# 1__schdoc.net
KiCad netlist of a schematic drawn in Altium Designer
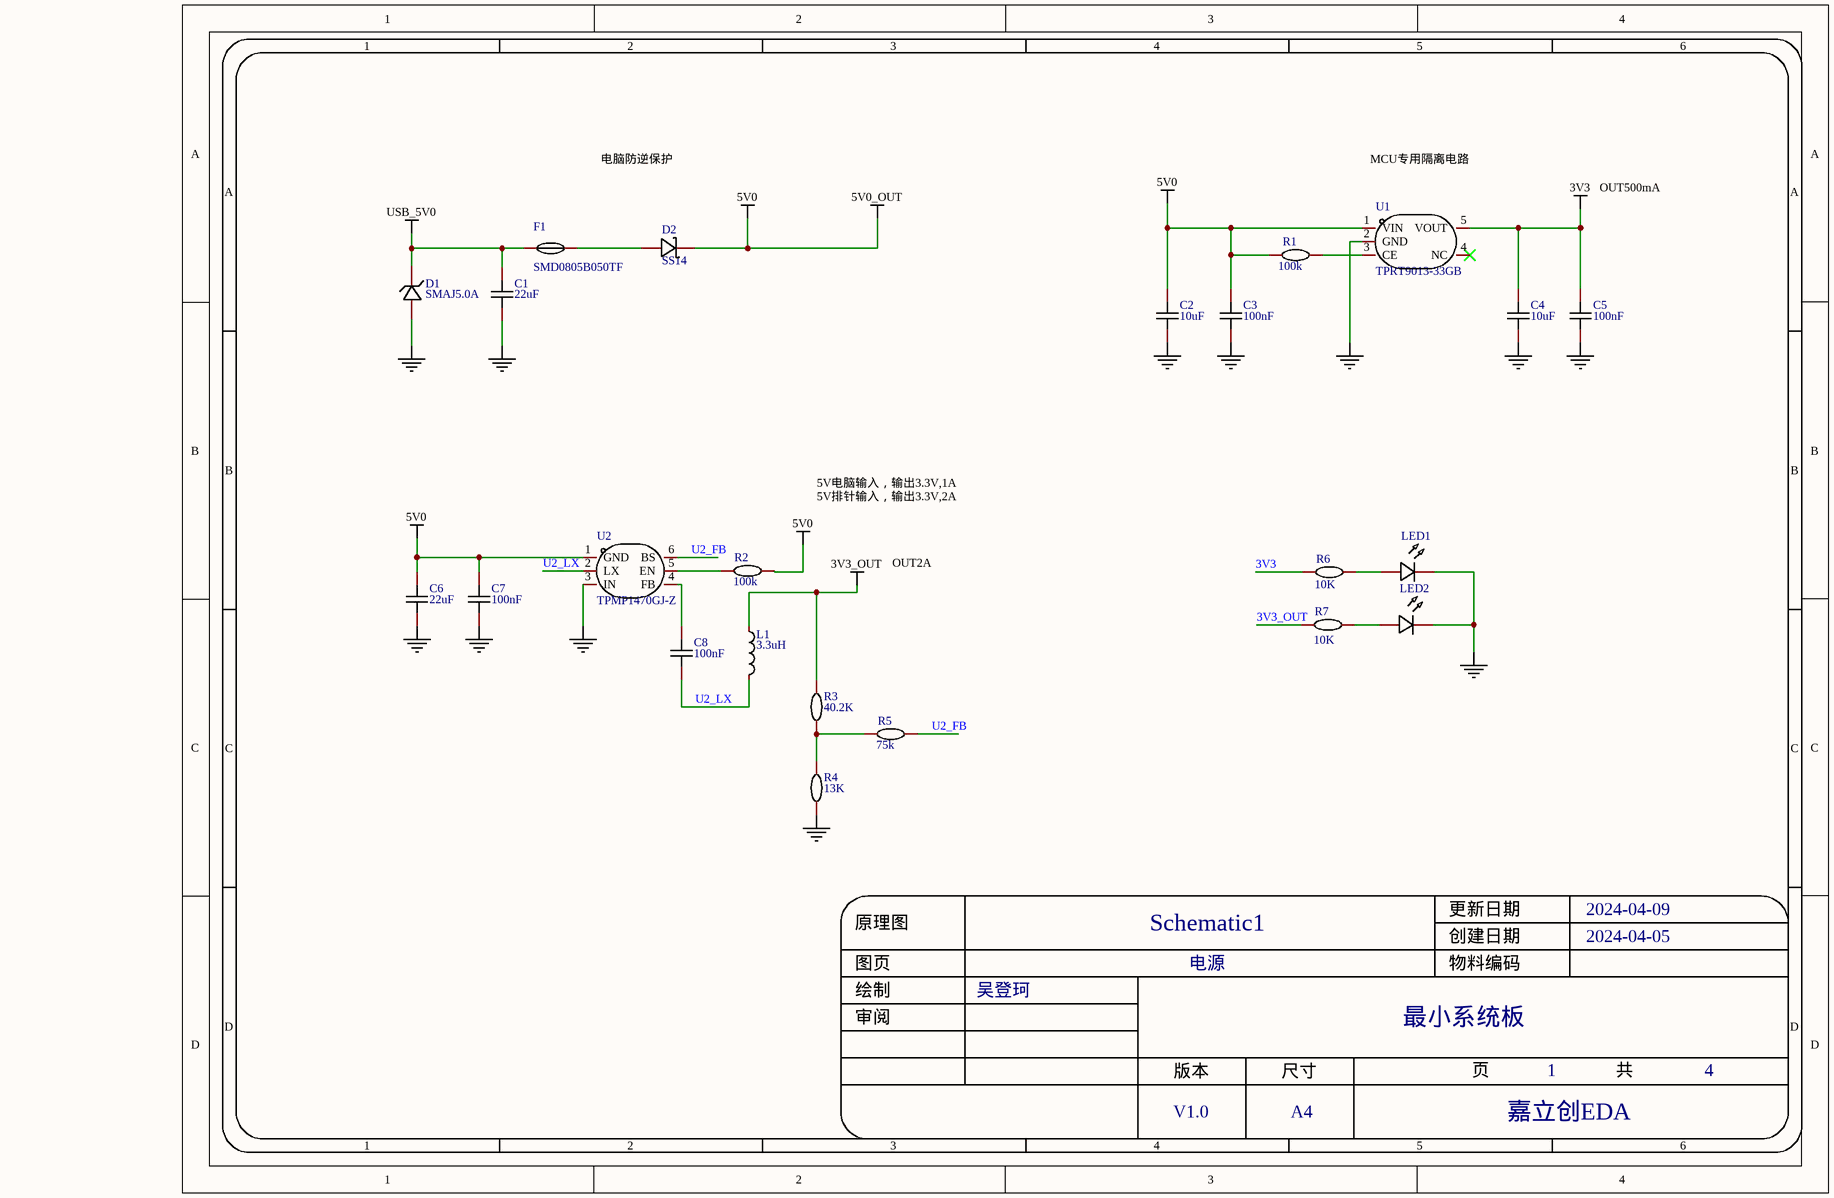
[diagram p0: 1_电源.schdoc.schdoc]

(export (version "E")
  (design (tool "Eeschema 10.0.6"))
  (components
    (comp (ref "C1")
      (value "22uF")
      (footprint "C1206")
      (fields (field (name "NAME") "22uF"))
      (libsource (lib "altium-import") (part "root_1_CAP_1206_"))
    )
    (comp (ref "C2")
      (value "10uF")
      (footprint "C0603")
      (fields (field (name "NAME") "10uF"))
      (libsource (lib "altium-import") (part "root_1_CAP_0603_"))
    )
    (comp (ref "C3")
      (value "100nF")
      (footprint "C0603")
      (fields (field (name "NAME") "100nF"))
      (libsource (lib "altium-import") (part "root_1_CAP_0603_"))
    )
    (comp (ref "C4")
      (value "10uF")
      (footprint "C0603")
      (fields (field (name "NAME") "10uF"))
      (libsource (lib "altium-import") (part "root_1_CAP_0603_"))
    )
    (comp (ref "C5")
      (value "100nF")
      (footprint "C0603")
      (fields (field (name "NAME") "100nF"))
      (libsource (lib "altium-import") (part "root_1_CAP_0603_"))
    )
    (comp (ref "C6")
      (value "22uF")
      (footprint "C1206")
      (fields (field (name "NAME") "22uF"))
      (libsource (lib "altium-import") (part "root_1_CAP_1206_"))
    )
    (comp (ref "C7")
      (value "100nF")
      (footprint "C0603")
      (fields (field (name "NAME") "100nF"))
      (libsource (lib "altium-import") (part "root_1_CAP_0603_"))
    )
    (comp (ref "C8")
      (value "100nF")
      (footprint "C0603")
      (fields (field (name "NAME") "100nF"))
      (libsource (lib "altium-import") (part "root_3_CAP_0603_"))
    )
    (comp (ref "D1")
      (value "SMAJ5.0A")
      (footprint "SMA_L4.4-W2.8-LS5.4-RD")
      (fields (field (name "NAME") "SMAJ5.0A") (field (name "MANUFACTURER") "晶导微电子"))
      (libsource (lib "altium-import") (part "root_3_SMAJ5.0A_C353442_"))
    )
    (comp (ref "D2")
      (value "SS14")
      (footprint "SMA_L4.3-W2.6-LS5.2-RD")
      (fields (field (name "NAME") "SS14") (field (name "MANUFACTURER") "onsemi(安森美)"))
      (libsource (lib "altium-import") (part "root_2_SS14_C83852_"))
    )
    (comp (ref "F1")
      (value "SMD0805B050TF")
      (footprint "F0805")
      (fields (field (name "NAME") "SMD0805B050TF") (field (name "MANUFACTURER") "Brightking(君耀电子)"))
      (libsource (lib "altium-import") (part "root_0_SMD0805B050TF_"))
    )
    (comp (ref "L1")
      (value "3.3uH")
      (footprint "IND-SMD_L7.3-W6.6")
      (fields
        (field (name "NAME") "3.3uH")
        (field (name "MANUFACTURER") "PSA(信昌电陶)")
        (field (name "MANUFACTURER PART") "MCS0630-2R2MPY1")
        (field (name "TOLERANCE") "±20%")
      )
      (libsource (lib "altium-import") (part "root_3_MCS0630-2R2MPY1_"))
    )
    (comp (ref "LED1")
      (value "LED_0603-R")
      (footprint "LED_0603")
      (libsource (lib "altium-import") (part "root_0_LED_0603-R_"))
    )
    (comp (ref "LED2")
      (value "LED_0603-R")
      (footprint "LED_0603")
      (libsource (lib "altium-import") (part "root_0_LED_0603-R_"))
    )
    (comp (ref "R1")
      (value "100k")
      (footprint "R0603")
      (fields (field (name "NAME") "100k"))
      (libsource (lib "altium-import") (part "root_0_Res_0603_"))
    )
    (comp (ref "R2")
      (value "100k")
      (footprint "R0603")
      (fields (field (name "NAME") "100k"))
      (libsource (lib "altium-import") (part "root_0_Res_0603_"))
    )
    (comp (ref "R3")
      (value "40.2K")
      (footprint "R0603")
      (fields (field (name "NAME") "40.2K"))
      (libsource (lib "altium-import") (part "root_1_Res_0603_"))
    )
    (comp (ref "R4")
      (value "13K")
      (footprint "R0603")
      (fields (field (name "NAME") "13K"))
      (libsource (lib "altium-import") (part "root_1_Res_0603_"))
    )
    (comp (ref "R5")
      (value "75k")
      (footprint "R0603")
      (fields (field (name "NAME") "75k"))
      (libsource (lib "altium-import") (part "root_0_Res_0603_"))
    )
    (comp (ref "R6")
      (value "10K")
      (footprint "R0603")
      (fields (field (name "NAME") "10K"))
      (libsource (lib "altium-import") (part "root_0_Res_0603_"))
    )
    (comp (ref "R7")
      (value "10K")
      (footprint "R0603")
      (fields (field (name "NAME") "10K"))
      (libsource (lib "altium-import") (part "root_0_Res_0603_"))
    )
    (comp (ref "U1")
      (value "TPRT9013-33GB")
      (footprint "SOT-23-5_L3.0-W1.7-P0.95-LS2.8-BL")
      (fields (field (name "NAME") "TPRT9013-33GB") (field (name "MANUFACTURER") "TECH PUBLIC(台舟)"))
      (libsource (lib "altium-import") (part "root_0_TPRT9013-33GB_"))
    )
    (comp (ref "U2")
      (value "TPMP1470GJ-Z")
      (footprint "SOT-23-6_L2.9-W1.6-P0.95-LS2.8-BL")
      (fields (field (name "NAME") "TPMP1470GJ-Z") (field (name "MANUFACTURER") "TECH PUBLIC(台舟)"))
      (libsource (lib "altium-import") (part "root_0_TPMP1470GJ-Z_"))
    )
  )
  (nets
    (net (code "1") (name "/U2_FB") (class "Default")
      (node (ref "R5") (pin "2") (pinfunction "2_2") (pintype "passive"))
      (node (ref "U2") (pin "6") (pinfunction "BS_6") (pintype "passive"))
    )
    (net (code "2") (name "/U2_LX") (class "Default")
      (node (ref "C8") (pin "2") (pinfunction "2_2") (pintype "passive"))
      (node (ref "L1") (pin "2") (pinfunction "2_2") (pintype "passive"))
      (node (ref "U2") (pin "2") (pinfunction "LX_2") (pintype "passive"))
    )
    (net (code "3") (name "3V3") (class "Default")
      (node (ref "C4") (pin "2") (pinfunction "2_2") (pintype "passive"))
      (node (ref "C5") (pin "2") (pinfunction "2_2") (pintype "passive"))
      (node (ref "R6") (pin "1") (pinfunction "1_1") (pintype "passive"))
      (node (ref "U1") (pin "5") (pinfunction "VOUT_5") (pintype "passive"))
    )
    (net (code "4") (name "3V3_OUT") (class "Default")
      (node (ref "L1") (pin "1") (pinfunction "1_1") (pintype "passive"))
      (node (ref "R3") (pin "2") (pinfunction "2_2") (pintype "passive"))
      (node (ref "R7") (pin "1") (pinfunction "1_1") (pintype "passive"))
    )
    (net (code "5") (name "5V0") (class "Default")
      (node (ref "C2") (pin "2") (pinfunction "2_2") (pintype "passive"))
      (node (ref "C3") (pin "2") (pinfunction "2_2") (pintype "passive"))
      (node (ref "C6") (pin "2") (pinfunction "2_2") (pintype "passive"))
      (node (ref "C7") (pin "2") (pinfunction "2_2") (pintype "passive"))
      (node (ref "D2") (pin "1") (pinfunction "K_1") (pintype "passive"))
      (node (ref "R1") (pin "1") (pinfunction "1_1") (pintype "passive"))
      (node (ref "R2") (pin "2") (pinfunction "2_2") (pintype "passive"))
      (node (ref "U1") (pin "1") (pinfunction "VIN_1") (pintype "passive"))
      (node (ref "U2") (pin "1") (pinfunction "GND_1") (pintype "passive"))
    )
    (net (code "6") (name "<NO NET>") (class "Default")
      (node (ref "C1") (pin "1") (pinfunction "1_1") (pintype "passive"))
      (node (ref "C2") (pin "1") (pinfunction "1_1") (pintype "passive"))
      (node (ref "C3") (pin "1") (pinfunction "1_1") (pintype "passive"))
      (node (ref "C4") (pin "1") (pinfunction "1_1") (pintype "passive"))
      (node (ref "C5") (pin "1") (pinfunction "1_1") (pintype "passive"))
      (node (ref "C6") (pin "1") (pinfunction "1_1") (pintype "passive"))
      (node (ref "C7") (pin "1") (pinfunction "1_1") (pintype "passive"))
      (node (ref "D1") (pin "2") (pinfunction "A_2") (pintype "passive"))
      (node (ref "LED1") (pin "1") (pinfunction "C_1") (pintype "passive"))
      (node (ref "LED2") (pin "1") (pinfunction "C_1") (pintype "passive"))
      (node (ref "R4") (pin "1") (pinfunction "1_1") (pintype "passive"))
      (node (ref "U1") (pin "2") (pinfunction "GND_2") (pintype "passive"))
      (node (ref "U2") (pin "3") (pinfunction "IN_3") (pintype "passive"))
    )
    (net (code "7") (name "Net-(D2-A)") (class "Default")
      (node (ref "D2") (pin "2") (pinfunction "A_2") (pintype "passive"))
      (node (ref "F1") (pin "2") (pinfunction "2_2") (pintype "passive"))
    )
    (net (code "8") (name "Net-(LED1-A)") (class "Default")
      (node (ref "LED1") (pin "2") (pinfunction "A_2") (pintype "passive"))
      (node (ref "R6") (pin "2") (pinfunction "2_2") (pintype "passive"))
    )
    (net (code "9") (name "Net-(LED2-A)") (class "Default")
      (node (ref "LED2") (pin "2") (pinfunction "A_2") (pintype "passive"))
      (node (ref "R7") (pin "2") (pinfunction "2_2") (pintype "passive"))
    )
    (net (code "10") (name "Net-(R3-Pad1)") (class "Default")
      (node (ref "R3") (pin "1") (pinfunction "1_1") (pintype "passive"))
      (node (ref "R4") (pin "2") (pinfunction "2_2") (pintype "passive"))
      (node (ref "R5") (pin "1") (pinfunction "1_1") (pintype "passive"))
    )
    (net (code "11") (name "Net-(U1-CE)") (class "Default")
      (node (ref "R1") (pin "2") (pinfunction "2_2") (pintype "passive"))
      (node (ref "U1") (pin "3") (pinfunction "CE_3") (pintype "passive"))
    )
    (net (code "12") (name "Net-(U2-EN)") (class "Default")
      (node (ref "R2") (pin "1") (pinfunction "1_1") (pintype "passive"))
      (node (ref "U2") (pin "5") (pinfunction "EN_5") (pintype "passive"))
    )
    (net (code "13") (name "Net-(U2-FB)") (class "Default")
      (node (ref "C8") (pin "1") (pinfunction "1_1") (pintype "passive"))
      (node (ref "U2") (pin "4") (pinfunction "FB_4") (pintype "passive"))
    )
    (net (code "14") (name "USB_5V0") (class "Default")
      (node (ref "C1") (pin "2") (pinfunction "2_2") (pintype "passive"))
      (node (ref "D1") (pin "1") (pinfunction "C_1") (pintype "passive"))
      (node (ref "F1") (pin "1") (pinfunction "1_1") (pintype "passive"))
    )
    (net (code "15") (name "unconnected-(U1-NC-Pad4)") (class "Default")
      (node (ref "U1") (pin "4") (pinfunction "NC_4") (pintype "passive+no_connect"))
    )
  )
)
